# schematic.net
KiCad netlist of a schematic drawn in EAGLE
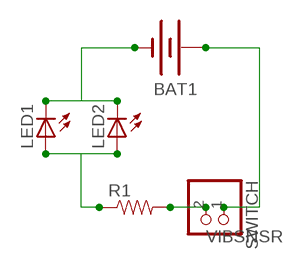
[diagram p0: schematic, sheet 1]

(export (version "E")
  (design (tool "Eeschema 10.0.6"))
  (components
    (comp (ref "BAT1")
      (value "BATTERY12PTH")
      (footprint "eagle-import:BATTCON_12MM_PTH")
      (libsource (lib "eagle-import") (part "BATTERY12PTH"))
    )
    (comp (ref "LED1")
      (value "LED5MM")
      (footprint "eagle-import:LED5MM")
      (libsource (lib "eagle-import") (part "LED5MM"))
    )
    (comp (ref "LED2")
      (value "LED5MM")
      (footprint "eagle-import:LED5MM")
      (libsource (lib "eagle-import") (part "LED5MM"))
    )
    (comp (ref "R1")
      (value "RESISTORKIT")
      (footprint "eagle-import:AXIAL-0.3-KIT")
      (libsource (lib "eagle-import") (part "RESISTORKIT"))
    )
    (comp (ref "SWITCH")
      (value "PINHD-1X2")
      (footprint "eagle-import:1X02")
      (libsource (lib "eagle-import") (part "PINHD-1X2"))
    )
  )
  (nets
    (net (code "1") (name "/VIBSNSR") (class "Default")
      (node (ref "BAT1") (pin "VCC@1") (pinfunction "+_VCC@1") (pintype "power_in"))
      (node (ref "SWITCH") (pin "1") (pinfunction "1_1") (pintype "passive"))
    )
    (net (code "2") (name "Net-(BAT1--)") (class "Default")
      (node (ref "BAT1") (pin "GND") (pinfunction "-_GND") (pintype "power_in"))
      (node (ref "LED1") (pin "K") (pinfunction "C_K") (pintype "passive"))
      (node (ref "LED2") (pin "K") (pinfunction "C_K") (pintype "passive"))
    )
    (net (code "3") (name "Net-(R1-1)") (class "Default")
      (node (ref "LED1") (pin "A") (pinfunction "A_A") (pintype "passive"))
      (node (ref "LED2") (pin "A") (pinfunction "A_A") (pintype "passive"))
      (node (ref "R1") (pin "P$1") (pinfunction "1_P$1") (pintype "passive"))
    )
    (net (code "4") (name "Net-(R1-2)") (class "Default")
      (node (ref "R1") (pin "P$2") (pinfunction "2_P$2") (pintype "passive"))
      (node (ref "SWITCH") (pin "2") (pinfunction "2_2") (pintype "passive"))
    )
  )
)
